# SCH_XT60_Power_Bar_9X.net
KiCad netlist of a schematic drawn in EasyEDA
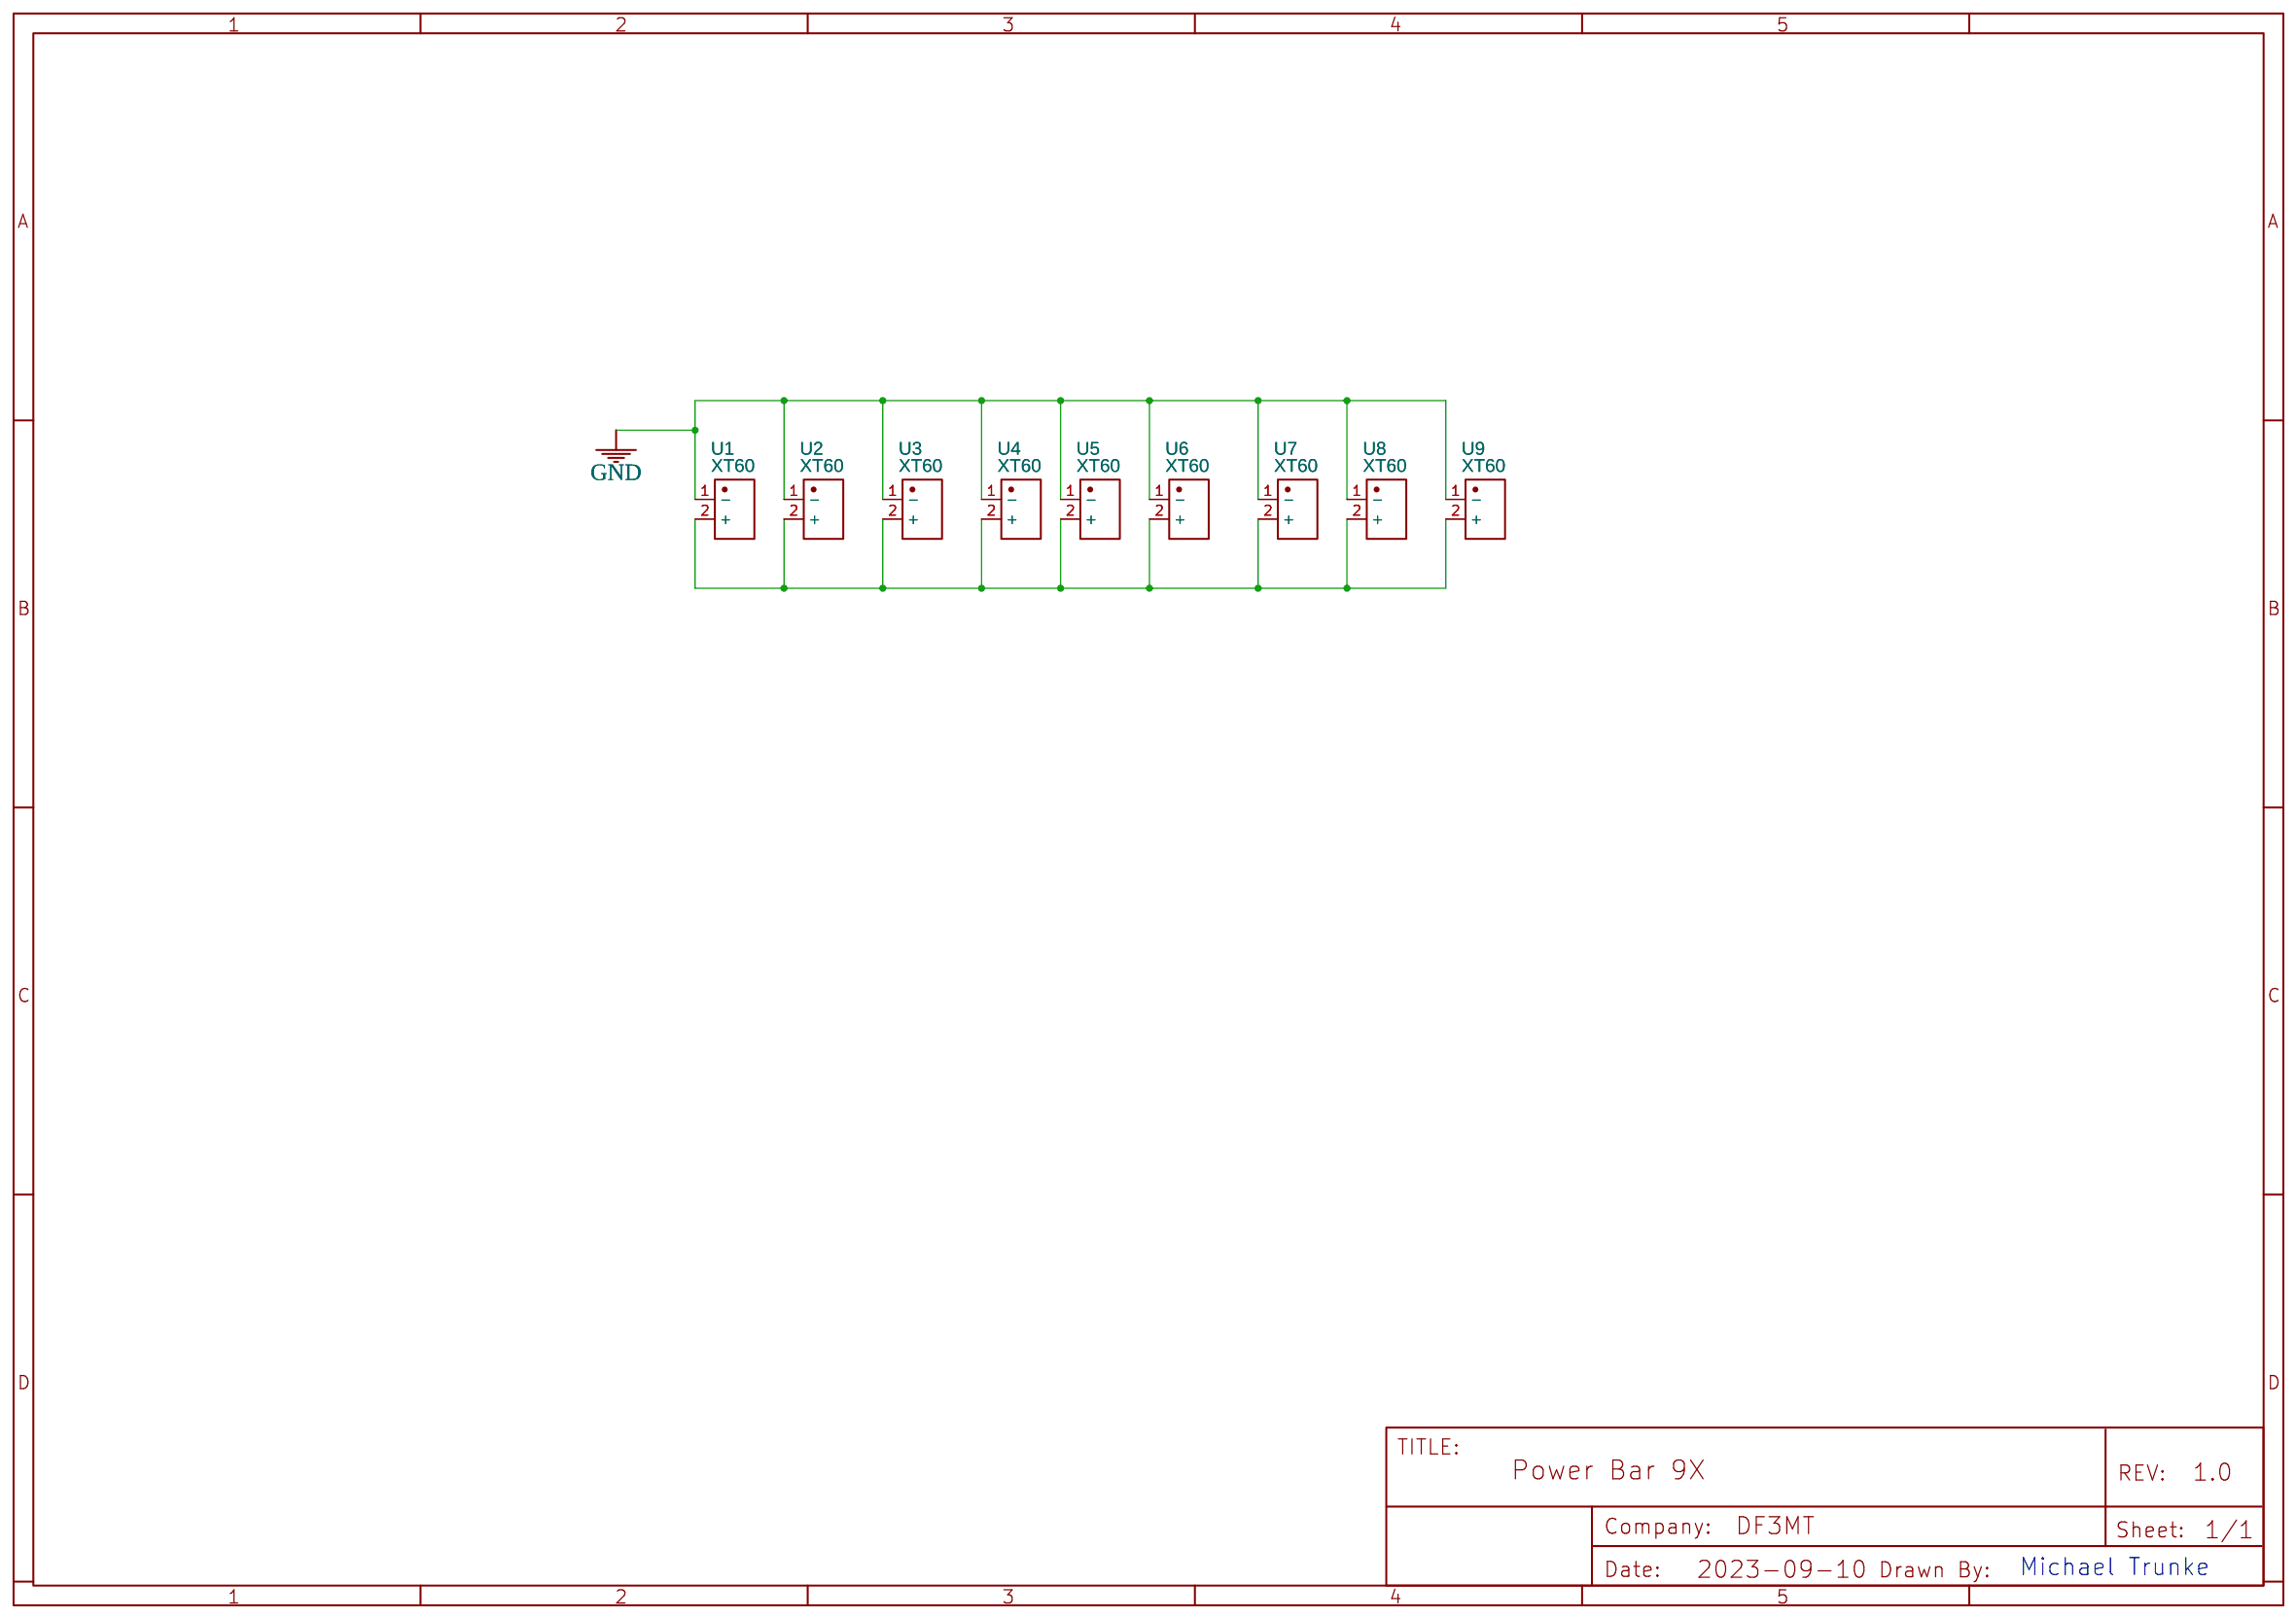
[diagram p0: schematic sheet]

(export (version "E")
  (design (tool "Eeschema 10.0.6"))
  (components
    (comp (ref "U1")
      (value "XT60")
      (fields (field (name "Manufacturer") "AMASS(艾迈斯)"))
      (libsource (lib "") (part "XT60"))
    )
    (comp (ref "U2")
      (value "XT60")
      (fields (field (name "Manufacturer") "AMASS(艾迈斯)"))
      (libsource (lib "") (part "XT60"))
    )
    (comp (ref "U3")
      (value "XT60")
      (fields (field (name "Manufacturer") "AMASS(艾迈斯)"))
      (libsource (lib "") (part "XT60"))
    )
    (comp (ref "U4")
      (value "XT60")
      (fields (field (name "Manufacturer") "AMASS(艾迈斯)"))
      (libsource (lib "") (part "XT60"))
    )
    (comp (ref "U5")
      (value "XT60")
      (fields (field (name "Manufacturer") "AMASS(艾迈斯)"))
      (libsource (lib "") (part "XT60"))
    )
    (comp (ref "U6")
      (value "XT60")
      (fields (field (name "Manufacturer") "AMASS(艾迈斯)"))
      (libsource (lib "") (part "XT60"))
    )
    (comp (ref "U7")
      (value "XT60")
      (fields (field (name "Manufacturer") "AMASS(艾迈斯)"))
      (libsource (lib "") (part "XT60"))
    )
    (comp (ref "U8")
      (value "XT60")
      (fields (field (name "Manufacturer") "AMASS(艾迈斯)"))
      (libsource (lib "") (part "XT60"))
    )
    (comp (ref "U9")
      (value "XT60")
      (fields (field (name "Manufacturer") "AMASS(艾迈斯)"))
      (libsource (lib "") (part "XT60"))
    )
  )
  (nets
    (net (code "1") (name "GND") (class "Default")
      (node (ref "U1") (pin "1") (pinfunction "-_1") (pintype "unspecified"))
      (node (ref "U2") (pin "1") (pinfunction "-_1") (pintype "unspecified"))
      (node (ref "U3") (pin "1") (pinfunction "-_1") (pintype "unspecified"))
      (node (ref "U4") (pin "1") (pinfunction "-_1") (pintype "unspecified"))
      (node (ref "U5") (pin "1") (pinfunction "-_1") (pintype "unspecified"))
      (node (ref "U6") (pin "1") (pinfunction "-_1") (pintype "unspecified"))
      (node (ref "U7") (pin "1") (pinfunction "-_1") (pintype "unspecified"))
      (node (ref "U8") (pin "1") (pinfunction "-_1") (pintype "unspecified"))
      (node (ref "U9") (pin "1") (pinfunction "-_1") (pintype "unspecified"))
    )
    (net (code "2") (name "Net-(U1-+)") (class "Default")
      (node (ref "U1") (pin "2") (pinfunction "+_2") (pintype "unspecified"))
      (node (ref "U2") (pin "2") (pinfunction "+_2") (pintype "unspecified"))
      (node (ref "U3") (pin "2") (pinfunction "+_2") (pintype "unspecified"))
      (node (ref "U4") (pin "2") (pinfunction "+_2") (pintype "unspecified"))
      (node (ref "U5") (pin "2") (pinfunction "+_2") (pintype "unspecified"))
      (node (ref "U6") (pin "2") (pinfunction "+_2") (pintype "unspecified"))
      (node (ref "U7") (pin "2") (pinfunction "+_2") (pintype "unspecified"))
      (node (ref "U8") (pin "2") (pinfunction "+_2") (pintype "unspecified"))
      (node (ref "U9") (pin "2") (pinfunction "+_2") (pintype "unspecified"))
    )
  )
)
